# Analog.net
KiCad netlist of a schematic drawn in Altium Designer
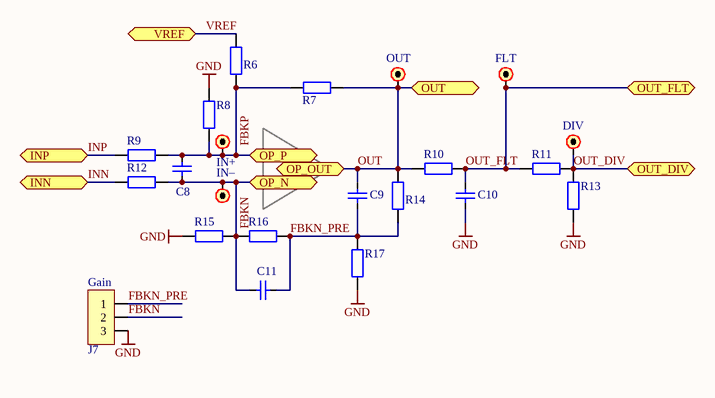
[diagram p0: Analog.SchDoc]

(export (version "E")
  (design (tool "Eeschema 10.0.6"))
  (components
    (comp (ref "C8")
      (value "? F")
      (footprint "0805C_RF_M")
      (description "Capacitor")
      (fields (field (name "TOLERANCE") "?") (field (name "MANUFACTURER") "Generic Brand"))
      (libsource (lib "AG.Generic") (part "C"))
    )
    (comp (ref "C9")
      (value "? F")
      (footprint "0805C_RF_M")
      (description "Capacitor")
      (fields (field (name "TOLERANCE") "?") (field (name "MANUFACTURER") "Generic Brand"))
      (libsource (lib "AG.Generic") (part "C"))
    )
    (comp (ref "C10")
      (value "? F")
      (footprint "0805C_RF_M")
      (description "Capacitor")
      (fields (field (name "TOLERANCE") "?") (field (name "MANUFACTURER") "Generic Brand"))
      (libsource (lib "AG.Generic") (part "C"))
    )
    (comp (ref "C11")
      (value "? F")
      (footprint "0805C_RF_M")
      (description "Capacitor")
      (fields (field (name "TOLERANCE") "?") (field (name "MANUFACTURER") "Generic Brand"))
      (libsource (lib "AG.Generic") (part "C"))
    )
    (comp (ref "J7")
      (value "Gain")
      (footprint "AG.Connectors:HEADER-2.54-3P1")
      (description "Generic Pin Header 3x1")
      (libsource (lib "AG.Connectors") (part "PINHDR-3P1"))
    )
    (comp (ref "R6")
      (value "? R")
      (footprint "0805R_RF_M")
      (description "Resistor")
      (fields (field (name "TOLERANCE") "?") (field (name "MANUFACTURER") "Generic Brand"))
      (libsource (lib "AG.Generic") (part "R"))
    )
    (comp (ref "R7")
      (value "? R")
      (footprint "0805R_RF_M")
      (description "Resistor")
      (fields (field (name "TOLERANCE") "?") (field (name "MANUFACTURER") "Generic Brand"))
      (libsource (lib "AG.Generic") (part "R"))
    )
    (comp (ref "R8")
      (value "? R")
      (footprint "0805R_RF_M")
      (description "Resistor")
      (fields (field (name "TOLERANCE") "?") (field (name "MANUFACTURER") "Generic Brand"))
      (libsource (lib "AG.Generic") (part "R"))
    )
    (comp (ref "R9")
      (value "? R")
      (footprint "0805R_RF_M")
      (description "Resistor")
      (fields (field (name "TOLERANCE") "?") (field (name "MANUFACTURER") "Generic Brand"))
      (libsource (lib "AG.Generic") (part "R"))
    )
    (comp (ref "R10")
      (value "? R")
      (footprint "0805R_RF_M")
      (description "Resistor")
      (fields (field (name "TOLERANCE") "?") (field (name "MANUFACTURER") "Generic Brand"))
      (libsource (lib "AG.Generic") (part "R"))
    )
    (comp (ref "R11")
      (value "? R")
      (footprint "0805R_RF_M")
      (description "Resistor")
      (fields (field (name "TOLERANCE") "?") (field (name "MANUFACTURER") "Generic Brand"))
      (libsource (lib "AG.Generic") (part "R"))
    )
    (comp (ref "R12")
      (value "? R")
      (footprint "0805R_RF_M")
      (description "Resistor")
      (fields (field (name "TOLERANCE") "?") (field (name "MANUFACTURER") "Generic Brand"))
      (libsource (lib "AG.Generic") (part "R"))
    )
    (comp (ref "R13")
      (value "? R")
      (footprint "0805R_RF_M")
      (description "Resistor")
      (fields (field (name "TOLERANCE") "?") (field (name "MANUFACTURER") "Generic Brand"))
      (libsource (lib "AG.Generic") (part "R"))
    )
    (comp (ref "R14")
      (value "? R")
      (footprint "0805R_RF_M")
      (description "Resistor")
      (fields (field (name "TOLERANCE") "?") (field (name "MANUFACTURER") "Generic Brand"))
      (libsource (lib "AG.Generic") (part "R"))
    )
    (comp (ref "R15")
      (value "? R")
      (footprint "0805R_RF_M")
      (description "Resistor")
      (fields (field (name "TOLERANCE") "?") (field (name "MANUFACTURER") "Generic Brand"))
      (libsource (lib "AG.Generic") (part "R"))
    )
    (comp (ref "R16")
      (value "? R")
      (footprint "0805R_RF_M")
      (description "Resistor")
      (fields (field (name "TOLERANCE") "?") (field (name "MANUFACTURER") "Generic Brand"))
      (libsource (lib "AG.Generic") (part "R"))
    )
    (comp (ref "R17")
      (value "? R")
      (footprint "0805R_RF_M")
      (description "Resistor")
      (fields (field (name "TOLERANCE") "?") (field (name "MANUFACTURER") "Generic Brand"))
      (libsource (lib "AG.Generic") (part "R"))
    )
    (comp (ref "TP5")
      (value "OUT")
      (footprint "PAD_R_1.5MM")
      (description "Test Point / Pad")
      (libsource (lib "AG.Misc") (part "Test Point"))
    )
    (comp (ref "TP6")
      (value "FLT")
      (footprint "PAD_R_1.5MM")
      (description "Test Point / Pad")
      (libsource (lib "AG.Misc") (part "Test Point"))
    )
    (comp (ref "TP7")
      (value "DIV")
      (footprint "PAD_R_1.5MM")
      (description "Test Point / Pad")
      (libsource (lib "AG.Misc") (part "Test Point"))
    )
    (comp (ref "TP8")
      (value "IN+")
      (footprint "PAD_R_1.5MM")
      (description "Test Point / Pad")
      (libsource (lib "AG.Misc") (part "Test Point"))
    )
    (comp (ref "TP9")
      (value "IN–")
      (footprint "PAD_R_1.5MM")
      (description "Test Point / Pad")
      (libsource (lib "AG.Misc") (part "Test Point"))
    )
  )
  (nets
    (net (code "1") (name "/FBKN") (class "Default")
      (node (ref "C11") (pin "2") (pinfunction "2_2") (pintype "passive"))
      (node (ref "C8") (pin "2") (pinfunction "2_2") (pintype "passive"))
      (node (ref "J7") (pin "2") (pinfunction "2_2") (pintype "passive"))
      (node (ref "R12") (pin "2") (pintype "passive"))
      (node (ref "R15") (pin "2") (pintype "passive"))
      (node (ref "R16") (pin "1") (pintype "passive"))
      (node (ref "TP9") (pin "1") (pinfunction "1_1") (pintype "passive"))
    )
    (net (code "2") (name "/FBKN_PRE") (class "Default")
      (node (ref "C11") (pin "1") (pinfunction "1_1") (pintype "passive"))
      (node (ref "C9") (pin "1") (pinfunction "1_1") (pintype "passive"))
      (node (ref "J7") (pin "1") (pinfunction "1_1") (pintype "passive"))
      (node (ref "R14") (pin "1") (pintype "passive"))
      (node (ref "R16") (pin "2") (pintype "passive"))
      (node (ref "R17") (pin "2") (pintype "passive"))
    )
    (net (code "3") (name "/FBKP") (class "Default")
      (node (ref "C8") (pin "1") (pinfunction "1_1") (pintype "passive"))
      (node (ref "R6") (pin "2") (pintype "passive"))
      (node (ref "R7") (pin "2") (pintype "passive"))
      (node (ref "R8") (pin "1") (pintype "passive"))
      (node (ref "R9") (pin "1") (pintype "passive"))
      (node (ref "TP8") (pin "1") (pinfunction "1_1") (pintype "passive"))
    )
    (net (code "4") (name "/INN") (class "Default") (node (ref "R12") (pin "1") (pintype "passive")))
    (net (code "5") (name "/INP") (class "Default") (node (ref "R9") (pin "2") (pintype "passive")))
    (net (code "6") (name "/OUT") (class "Default")
      (node (ref "C9") (pin "2") (pinfunction "2_2") (pintype "passive"))
      (node (ref "R10") (pin "1") (pintype "passive"))
      (node (ref "R14") (pin "2") (pintype "passive"))
      (node (ref "R7") (pin "1") (pintype "passive"))
      (node (ref "TP5") (pin "1") (pinfunction "1_1") (pintype "passive"))
    )
    (net (code "7") (name "/OUT_DIV") (class "Default")
      (node (ref "R11") (pin "2") (pintype "passive"))
      (node (ref "R13") (pin "2") (pintype "passive"))
      (node (ref "TP7") (pin "1") (pinfunction "1_1") (pintype "passive"))
    )
    (net (code "8") (name "/OUT_FLT") (class "Default")
      (node (ref "C10") (pin "2") (pinfunction "2_2") (pintype "passive"))
      (node (ref "R10") (pin "2") (pintype "passive"))
      (node (ref "R11") (pin "1") (pintype "passive"))
      (node (ref "TP6") (pin "1") (pinfunction "1_1") (pintype "passive"))
    )
    (net (code "9") (name "/VREF") (class "Default") (node (ref "R6") (pin "1") (pintype "passive")))
    (net (code "10") (name "GND") (class "Default")
      (node (ref "C10") (pin "1") (pinfunction "1_1") (pintype "passive"))
      (node (ref "J7") (pin "3") (pinfunction "3_3") (pintype "passive"))
      (node (ref "R13") (pin "1") (pintype "passive"))
      (node (ref "R15") (pin "1") (pintype "passive"))
      (node (ref "R17") (pin "1") (pintype "passive"))
      (node (ref "R8") (pin "2") (pintype "passive"))
    )
  )
)
